# FPGA_power_supply.net
KiCad netlist of a schematic drawn in Altium Designer
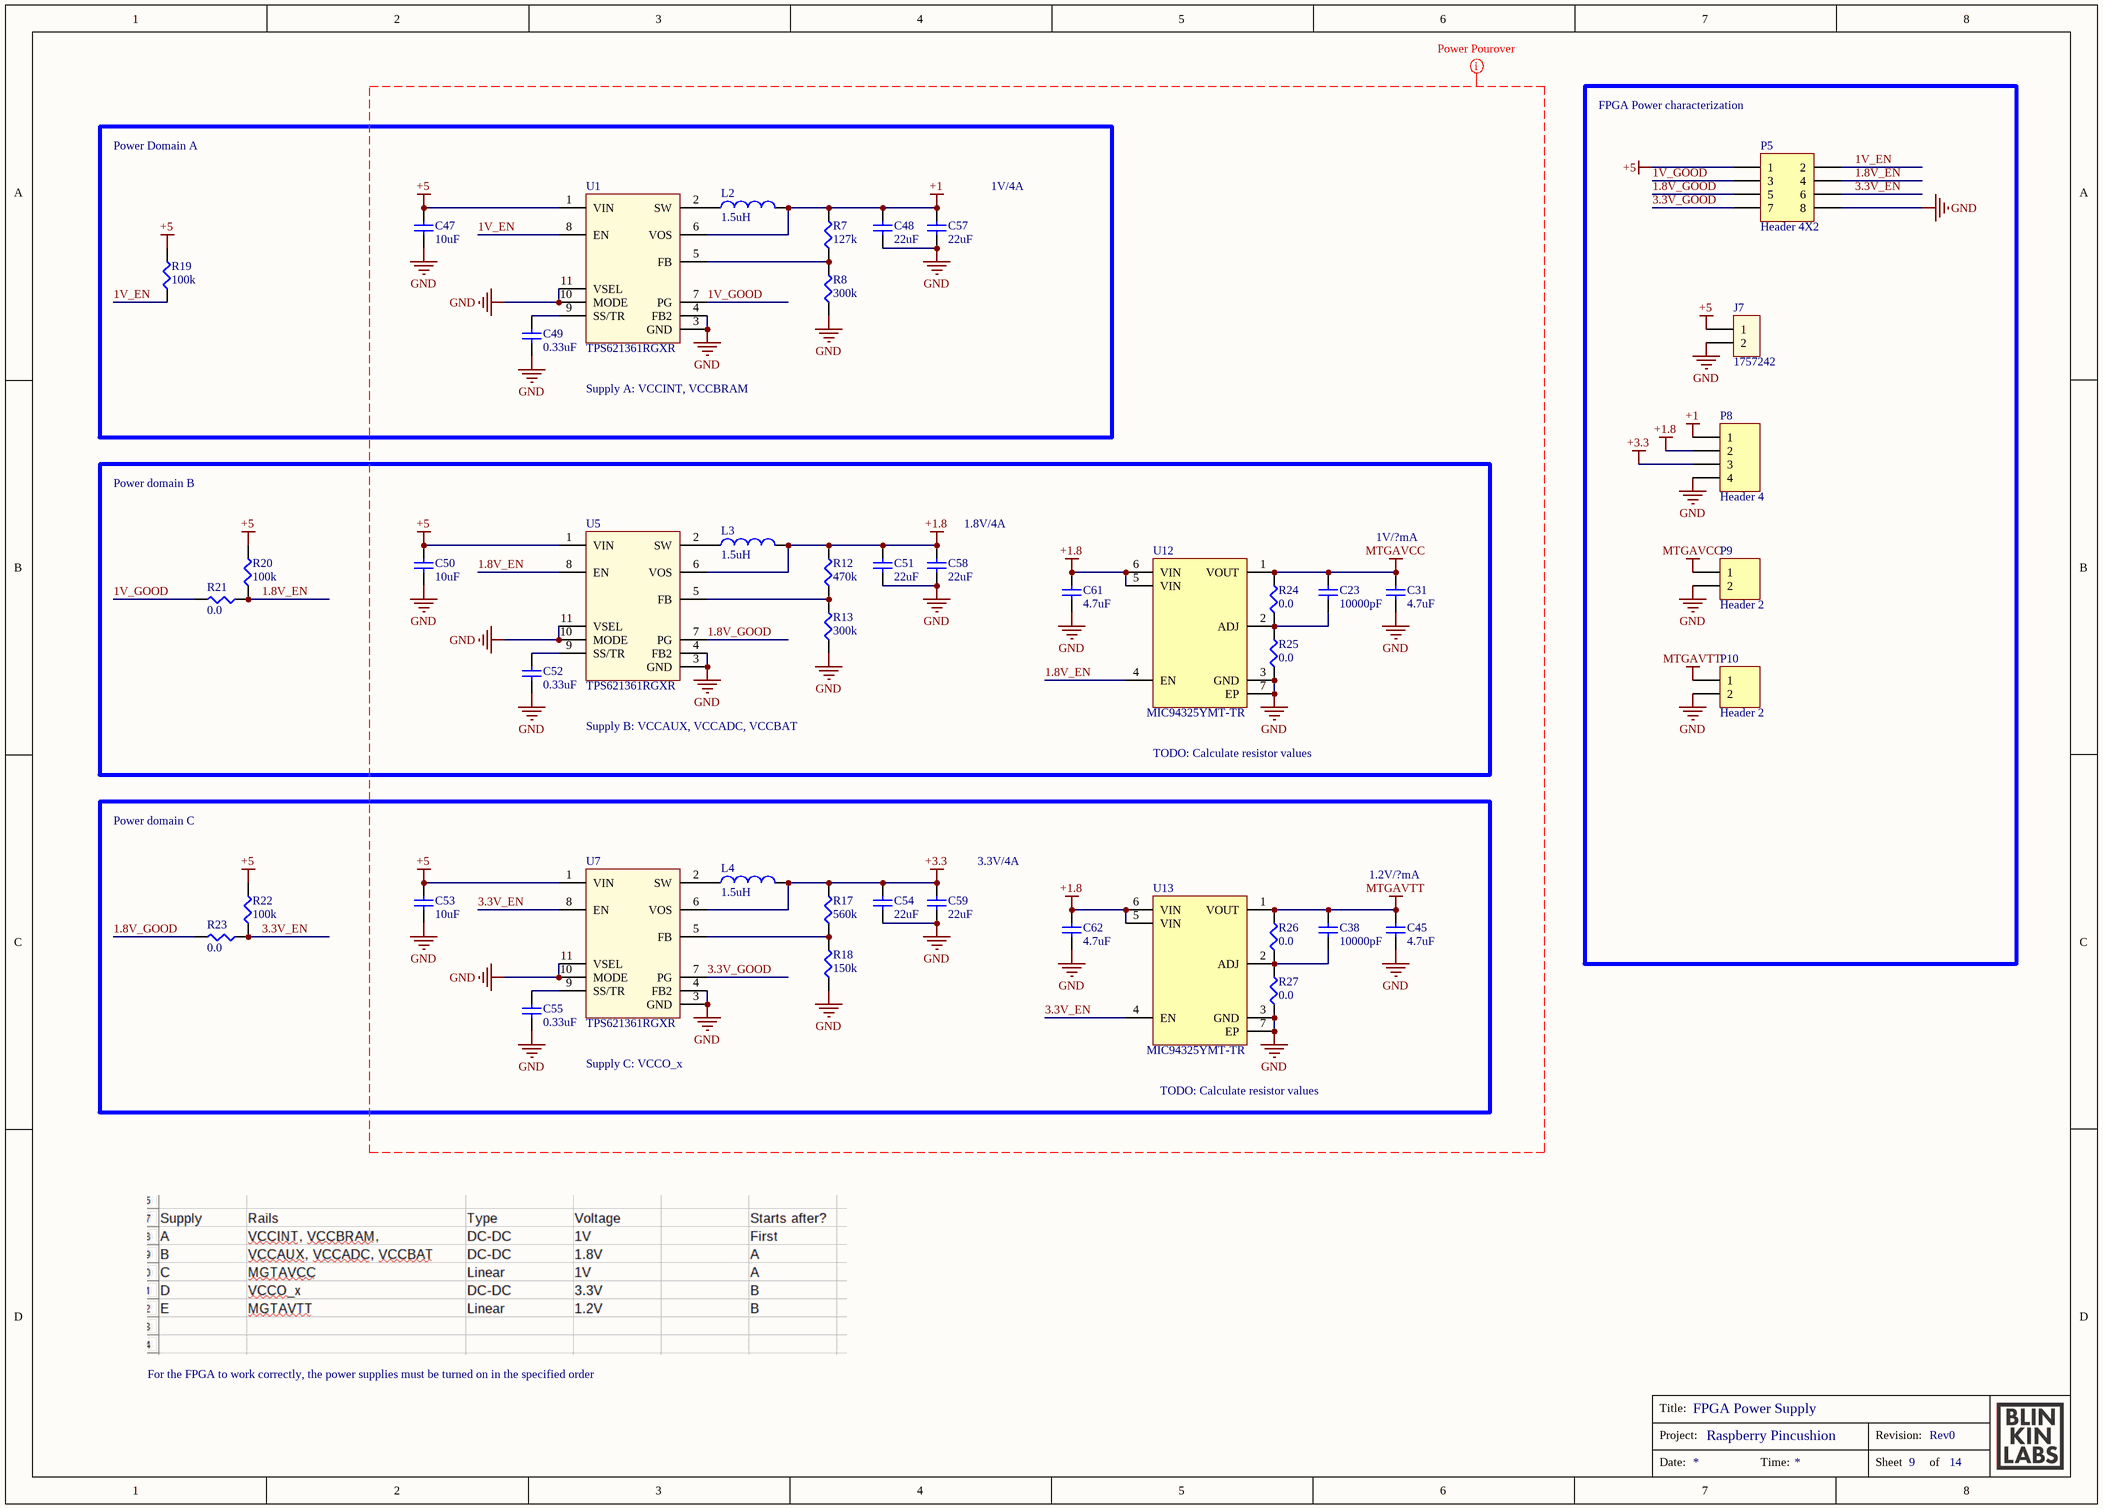
[diagram p0: FPGA power supply.SchDoc]

(export (version "E")
  (design (tool "Eeschema 10.0.6"))
  (components
    (comp (ref "C23")
      (value "10000pF")
      (footprint "CAPC1005X06L")
      (description "CAP CER 10000PF 16V X7R 0402")
      (fields
        (field (name "PARTNUMBER") "GRM155R71C103KA01D")
        (field (name "DIGI-KEY PART NUMBER") "490-1313-1-ND")
      )
      (libsource (lib "cap_murata") (part "CAPACITOR"))
    )
    (comp (ref "C31")
      (value "4.7uF")
      (footprint "CAPC1005X06L")
      (description "CAP CER 4.7UF 4V X5R 0402")
      (fields
        (field (name "PARTNUMBER") "GRM155R60G475ME47D")
        (field (name "DIGI-KEY PART NUMBER") "490-11980-1-ND")
      )
      (libsource (lib "cap_murata") (part "CAPACITOR"))
    )
    (comp (ref "C38")
      (value "10000pF")
      (footprint "CAPC1005X06L")
      (description "CAP CER 10000PF 16V X7R 0402")
      (fields
        (field (name "PARTNUMBER") "GRM155R71C103KA01D")
        (field (name "DIGI-KEY PART NUMBER") "490-1313-1-ND")
      )
      (libsource (lib "cap_murata") (part "CAPACITOR"))
    )
    (comp (ref "C45")
      (value "4.7uF")
      (footprint "CAPC1005X06L")
      (description "CAP CER 4.7UF 4V X5R 0402")
      (fields
        (field (name "PARTNUMBER") "GRM155R60G475ME47D")
        (field (name "DIGI-KEY PART NUMBER") "490-11980-1-ND")
      )
      (libsource (lib "cap_murata") (part "CAPACITOR"))
    )
    (comp (ref "C47")
      (value "10uF")
      (footprint "CAPC2012X10L")
      (description "CAP CER 10UF 10V X7R 0805")
      (fields
        (field (name "PARTNUMBER") "GRM21BR71A106KE51L")
        (field (name "DIGI-KEY PART NUMBER") "490-3905-1-ND")
      )
      (libsource (lib "cap_murata") (part "CAPACITOR"))
    )
    (comp (ref "C48")
      (value "22uF")
      (footprint "CAPC2012X10L")
      (description "CAP CER 22UF 10V X5R 0805")
      (fields
        (field (name "PARTNUMBER") "GRM219R61A226MEA0D")
        (field (name "DIGI-KEY PART NUMBER") "490-9951-1-ND")
      )
      (libsource (lib "cap_murata") (part "CAPACITOR"))
    )
    (comp (ref "C49")
      (value "0.33uF")
      (footprint "CAPC1005X06L")
      (description "CAP CER 0.33UF 6.3V X5R 0402")
      (fields
        (field (name "PARTNUMBER") "GRM155R60J334KE01D")
        (field (name "DIGI-KEY PART NUMBER") "490-3265-1-ND")
      )
      (libsource (lib "cap_murata") (part "CAPACITOR"))
    )
    (comp (ref "C50")
      (value "10uF")
      (footprint "CAPC2012X10L")
      (description "CAP CER 10UF 10V X7R 0805")
      (fields
        (field (name "PARTNUMBER") "GRM21BR71A106KE51L")
        (field (name "DIGI-KEY PART NUMBER") "490-3905-1-ND")
      )
      (libsource (lib "cap_murata") (part "CAPACITOR"))
    )
    (comp (ref "C51")
      (value "22uF")
      (footprint "CAPC2012X10L")
      (description "CAP CER 22UF 10V X5R 0805")
      (fields
        (field (name "PARTNUMBER") "GRM219R61A226MEA0D")
        (field (name "DIGI-KEY PART NUMBER") "490-9951-1-ND")
      )
      (libsource (lib "cap_murata") (part "CAPACITOR"))
    )
    (comp (ref "C52")
      (value "0.33uF")
      (footprint "CAPC1005X06L")
      (description "CAP CER 0.33UF 6.3V X5R 0402")
      (fields
        (field (name "PARTNUMBER") "GRM155R60J334KE01D")
        (field (name "DIGI-KEY PART NUMBER") "490-3265-1-ND")
      )
      (libsource (lib "cap_murata") (part "CAPACITOR"))
    )
    (comp (ref "C53")
      (value "10uF")
      (footprint "CAPC2012X10L")
      (description "CAP CER 10UF 10V X7R 0805")
      (fields
        (field (name "PARTNUMBER") "GRM21BR71A106KE51L")
        (field (name "DIGI-KEY PART NUMBER") "490-3905-1-ND")
      )
      (libsource (lib "cap_murata") (part "CAPACITOR"))
    )
    (comp (ref "C54")
      (value "22uF")
      (footprint "CAPC2012X10L")
      (description "CAP CER 22UF 10V X5R 0805")
      (fields
        (field (name "PARTNUMBER") "GRM219R61A226MEA0D")
        (field (name "DIGI-KEY PART NUMBER") "490-9951-1-ND")
      )
      (libsource (lib "cap_murata") (part "CAPACITOR"))
    )
    (comp (ref "C55")
      (value "0.33uF")
      (footprint "CAPC1005X06L")
      (description "CAP CER 0.33UF 6.3V X5R 0402")
      (fields
        (field (name "PARTNUMBER") "GRM155R60J334KE01D")
        (field (name "DIGI-KEY PART NUMBER") "490-3265-1-ND")
      )
      (libsource (lib "cap_murata") (part "CAPACITOR"))
    )
    (comp (ref "C57")
      (value "22uF")
      (footprint "CAPC2012X10L")
      (description "CAP CER 22UF 10V X5R 0805")
      (fields
        (field (name "PARTNUMBER") "GRM219R61A226MEA0D")
        (field (name "DIGI-KEY PART NUMBER") "490-9951-1-ND")
      )
      (libsource (lib "cap_murata") (part "CAPACITOR"))
    )
    (comp (ref "C58")
      (value "22uF")
      (footprint "CAPC2012X10L")
      (description "CAP CER 22UF 10V X5R 0805")
      (fields
        (field (name "PARTNUMBER") "GRM219R61A226MEA0D")
        (field (name "DIGI-KEY PART NUMBER") "490-9951-1-ND")
      )
      (libsource (lib "cap_murata") (part "CAPACITOR"))
    )
    (comp (ref "C59")
      (value "22uF")
      (footprint "CAPC2012X10L")
      (description "CAP CER 22UF 10V X5R 0805")
      (fields
        (field (name "PARTNUMBER") "GRM219R61A226MEA0D")
        (field (name "DIGI-KEY PART NUMBER") "490-9951-1-ND")
      )
      (libsource (lib "cap_murata") (part "CAPACITOR"))
    )
    (comp (ref "C61")
      (value "4.7uF")
      (footprint "CAPC1005X06L")
      (description "CAP CER 4.7UF 4V X5R 0402")
      (fields
        (field (name "PARTNUMBER") "GRM155R60G475ME47D")
        (field (name "DIGI-KEY PART NUMBER") "490-11980-1-ND")
      )
      (libsource (lib "cap_murata") (part "CAPACITOR"))
    )
    (comp (ref "C62")
      (value "4.7uF")
      (footprint "CAPC1005X06L")
      (description "CAP CER 4.7UF 4V X5R 0402")
      (fields
        (field (name "PARTNUMBER") "GRM155R60G475ME47D")
        (field (name "DIGI-KEY PART NUMBER") "490-11980-1-ND")
      )
      (libsource (lib "cap_murata") (part "CAPACITOR"))
    )
    (comp (ref "J7")
      (value "1757242")
      (footprint "1757242")
      (description "TERM BLOCK HDR 2POS 90DEG 5.08MM")
      (fields (field (name "MANUFACTURER") "Phoenix Contact") (field (name "PARTNUMBER") "1757268"))
      (libsource (lib "Blinkinlabs") (part "1757242"))
    )
    (comp (ref "L2")
      (value "1.5uH")
      (footprint "SWPA4030S")
      (description "1.5uH ±20% 3.34A 26mΩ SMD,4.0x4.0x3.0mm Power Inductors RoHS")
      (fields (field (name "PARTNUMBER") "SWPA4030S1R5NT") (field (name "LCSC PARTNUMBER") "C42100"))
      (libsource (lib "inductor_changjiang") (part "INDUCTOR"))
    )
    (comp (ref "L3")
      (value "1.5uH")
      (footprint "SWPA4030S")
      (description "1.5uH ±20% 3.34A 26mΩ SMD,4.0x4.0x3.0mm Power Inductors RoHS")
      (fields (field (name "PARTNUMBER") "SWPA4030S1R5NT") (field (name "LCSC PARTNUMBER") "C42100"))
      (libsource (lib "inductor_changjiang") (part "INDUCTOR"))
    )
    (comp (ref "L4")
      (value "1.5uH")
      (footprint "SWPA4030S")
      (description "1.5uH ±20% 3.34A 26mΩ SMD,4.0x4.0x3.0mm Power Inductors RoHS")
      (fields (field (name "PARTNUMBER") "SWPA4030S1R5NT") (field (name "LCSC PARTNUMBER") "C42100"))
      (libsource (lib "inductor_changjiang") (part "INDUCTOR"))
    )
    (comp (ref "P5")
      (value "Header 4X2")
      (footprint "HDR2X4")
      (description "Header, 4-Pin, Dual row")
      (fields (field (name "PUBLISHER") "Altium Limited"))
      (libsource (lib "Miscellaneous Connectors") (part "Header 4X2"))
    )
    (comp (ref "P8")
      (value "Header 4")
      (footprint "HDR1X4")
      (description "Header, 4-Pin")
      (fields (field (name "PUBLISHER") "Altium Limited"))
      (libsource (lib "Miscellaneous Connectors") (part "Header 4"))
    )
    (comp (ref "P9")
      (value "Header 2")
      (footprint "HDR1X2")
      (description "Header, 2-Pin")
      (fields (field (name "PUBLISHER") "Altium Limited"))
      (libsource (lib "Miscellaneous Connectors") (part "Header 2"))
    )
    (comp (ref "P10")
      (value "Header 2")
      (footprint "HDR1X2")
      (description "Header, 2-Pin")
      (fields (field (name "PUBLISHER") "Altium Limited"))
      (libsource (lib "Miscellaneous Connectors") (part "Header 2"))
    )
    (comp (ref "R7")
      (value "127k")
      (footprint "ERJ2G(0402)_L")
      (description "RES SMD 127K OHM 1% 1/10W 0402")
      (fields (field (name "PARTNUMBER") "ERJ-2RKF1273X") (field (name "DIGI-KEY PART NUMBER") "P127KLCT-ND"))
      (libsource (lib "res_panasonic_erj_xls") (part "RESISTOR"))
    )
    (comp (ref "R8")
      (value "300k")
      (footprint "ERJ2G(0402)_L")
      (description "RES SMD 300K OHM 1% 1/10W 0402")
      (fields (field (name "PARTNUMBER") "ERJ-2RKF3003X") (field (name "DIGI-KEY PART NUMBER") "P300KLCT-ND"))
      (libsource (lib "res_panasonic_erj_xls") (part "RESISTOR"))
    )
    (comp (ref "R12")
      (value "470k")
      (footprint "ERJ2G(0402)_L")
      (description "RES SMD 470K OHM 1% 1/5W 0402")
      (fields (field (name "PARTNUMBER") "ERJ-PA2F4703X") (field (name "DIGI-KEY PART NUMBER") "P17240CT-ND"))
      (libsource (lib "res_panasonic_erj_xls") (part "RESISTOR"))
    )
    (comp (ref "R13")
      (value "300k")
      (footprint "ERJ2G(0402)_L")
      (description "RES SMD 300K OHM 1% 1/10W 0402")
      (fields (field (name "PARTNUMBER") "ERJ-2RKF3003X") (field (name "DIGI-KEY PART NUMBER") "P300KLCT-ND"))
      (libsource (lib "res_panasonic_erj_xls") (part "RESISTOR"))
    )
    (comp (ref "R17")
      (value "560k")
      (footprint "ERJ2G(0402)_L")
      (description "RES SMD 560K OHM 1% 1/10W 0402")
      (fields (field (name "PARTNUMBER") "ERJ-2RKF5603X") (field (name "DIGI-KEY PART NUMBER") "P560KLCT-ND"))
      (libsource (lib "res_panasonic_erj_xls") (part "RESISTOR"))
    )
    (comp (ref "R18")
      (value "150k")
      (footprint "ERJ2G(0402)_L")
      (description "RES SMD 150K OHM 1% 1/5W 0402")
      (fields (field (name "PARTNUMBER") "ERJ-PA2F1503X") (field (name "DIGI-KEY PART NUMBER") "P17237CT-ND"))
      (libsource (lib "res_panasonic_erj_xls") (part "RESISTOR"))
    )
    (comp (ref "R19")
      (value "100k")
      (footprint "ERJ2G(0402)_L")
      (description "RES SMD 100K OHM 1% 1/5W 0402")
      (fields (field (name "PARTNUMBER") "ERJ-PA2F1003X") (field (name "DIGI-KEY PART NUMBER") "P17236CT-ND"))
      (libsource (lib "res_panasonic_erj_xls") (part "RESISTOR"))
    )
    (comp (ref "R20")
      (value "100k")
      (footprint "ERJ2G(0402)_L")
      (description "RES SMD 100K OHM 1% 1/5W 0402")
      (fields (field (name "PARTNUMBER") "ERJ-PA2F1003X") (field (name "DIGI-KEY PART NUMBER") "P17236CT-ND"))
      (libsource (lib "res_panasonic_erj_xls") (part "RESISTOR"))
    )
    (comp (ref "R21")
      (value "0.0")
      (footprint "ERJ2G(0402)_L")
      (description "RES SMD 0.0OHM JUMPER 1/10W 0402")
      (fields (field (name "PARTNUMBER") "ERJ-2GE0R00X") (field (name "DIGI-KEY PART NUMBER") "P0.0JCT-ND"))
      (libsource (lib "res_panasonic_erj_xls") (part "RESISTOR"))
    )
    (comp (ref "R22")
      (value "100k")
      (footprint "ERJ2G(0402)_L")
      (description "RES SMD 100K OHM 1% 1/5W 0402")
      (fields (field (name "PARTNUMBER") "ERJ-PA2F1003X") (field (name "DIGI-KEY PART NUMBER") "P17236CT-ND"))
      (libsource (lib "res_panasonic_erj_xls") (part "RESISTOR"))
    )
    (comp (ref "R23")
      (value "0.0")
      (footprint "ERJ2G(0402)_L")
      (description "RES SMD 0.0OHM JUMPER 1/10W 0402")
      (fields (field (name "PARTNUMBER") "ERJ-2GE0R00X") (field (name "DIGI-KEY PART NUMBER") "P0.0JCT-ND"))
      (libsource (lib "res_panasonic_erj_xls") (part "RESISTOR"))
    )
    (comp (ref "R24")
      (value "0.0")
      (footprint "ERJ2G(0402)_L")
      (description "RES SMD 0.0OHM JUMPER 1/10W 0402")
      (fields (field (name "PARTNUMBER") "ERJ-2GE0R00X") (field (name "DIGI-KEY PART NUMBER") "P0.0JCT-ND"))
      (libsource (lib "res_panasonic_erj_xls") (part "RESISTOR"))
    )
    (comp (ref "R25")
      (value "0.0")
      (footprint "ERJ2G(0402)_L")
      (description "RES SMD 0.0OHM JUMPER 1/10W 0402")
      (fields (field (name "PARTNUMBER") "ERJ-2GE0R00X") (field (name "DIGI-KEY PART NUMBER") "P0.0JCT-ND"))
      (libsource (lib "res_panasonic_erj_xls") (part "RESISTOR"))
    )
    (comp (ref "R26")
      (value "0.0")
      (footprint "ERJ2G(0402)_L")
      (description "RES SMD 0.0OHM JUMPER 1/10W 0402")
      (fields (field (name "PARTNUMBER") "ERJ-2GE0R00X") (field (name "DIGI-KEY PART NUMBER") "P0.0JCT-ND"))
      (libsource (lib "res_panasonic_erj_xls") (part "RESISTOR"))
    )
    (comp (ref "R27")
      (value "0.0")
      (footprint "ERJ2G(0402)_L")
      (description "RES SMD 0.0OHM JUMPER 1/10W 0402")
      (fields (field (name "PARTNUMBER") "ERJ-2GE0R00X") (field (name "DIGI-KEY PART NUMBER") "P0.0JCT-ND"))
      (libsource (lib "res_panasonic_erj_xls") (part "RESISTOR"))
    )
    (comp (ref "U1")
      (value "TPS621361RGXR")
      (footprint "RGX0011A")
      (description "IC REG BUCK ADJUSTABLE 4A 11VQFN")
      (fields
        (field (name "MANUFACTURER") "Texas Instruments")
        (field (name "DIGIKEY PARTNUMBER") "296-50117-2-ND")
      )
      (libsource (lib "Blinkinlabs") (part "TPS621361RGXR"))
    )
    (comp (ref "U5")
      (value "TPS621361RGXR")
      (footprint "RGX0011A")
      (description "IC REG BUCK ADJUSTABLE 4A 11VQFN")
      (fields
        (field (name "MANUFACTURER") "Texas Instruments")
        (field (name "DIGIKEY PARTNUMBER") "296-50117-2-ND")
      )
      (libsource (lib "Blinkinlabs") (part "TPS621361RGXR"))
    )
    (comp (ref "U7")
      (value "TPS621361RGXR")
      (footprint "RGX0011A")
      (description "IC REG BUCK ADJUSTABLE 4A 11VQFN")
      (fields
        (field (name "MANUFACTURER") "Texas Instruments")
        (field (name "DIGIKEY PARTNUMBER") "296-50117-2-ND")
      )
      (libsource (lib "Blinkinlabs") (part "TPS621361RGXR"))
    )
    (comp (ref "U12")
      (value "MIC94325YMT-TR")
      (footprint "QFN50P160X160X60_HS-7N")
      (description "500mA LDO with  Ripple Blocker Technology")
      (fields
        (field (name "MANUFACTURER") "Microchip Technology")
        (field (name "DIGIKEY PARTNUMBER") "576-4164-2-ND")
      )
      (libsource (lib "Blinkinlabs") (part "MIC94325YMT-TR"))
    )
    (comp (ref "U13")
      (value "MIC94325YMT-TR")
      (footprint "QFN50P160X160X60_HS-7N")
      (description "500mA LDO with  Ripple Blocker Technology")
      (fields
        (field (name "MANUFACTURER") "Microchip Technology")
        (field (name "DIGIKEY PARTNUMBER") "576-4164-2-ND")
      )
      (libsource (lib "Blinkinlabs") (part "MIC94325YMT-TR"))
    )
  )
  (nets
    (net (code "1") (name "+1") (class "Default")
      (node (ref "C48") (pin "1") (pinfunction "1_1") (pintype "passive"))
      (node (ref "C57") (pin "1") (pinfunction "1_1") (pintype "passive"))
      (node (ref "L2") (pin "2") (pinfunction "2_2") (pintype "passive"))
      (node (ref "P8") (pin "1") (pinfunction "1_1") (pintype "passive"))
      (node (ref "R7") (pin "2") (pinfunction "2_2") (pintype "passive"))
      (node (ref "U1") (pin "6") (pinfunction "VOS_6") (pintype "passive"))
    )
    (net (code "2") (name "+1.8") (class "Default")
      (node (ref "C51") (pin "1") (pinfunction "1_1") (pintype "passive"))
      (node (ref "C58") (pin "1") (pinfunction "1_1") (pintype "passive"))
      (node (ref "C61") (pin "2") (pinfunction "2_2") (pintype "passive"))
      (node (ref "C62") (pin "2") (pinfunction "2_2") (pintype "passive"))
      (node (ref "L3") (pin "2") (pinfunction "2_2") (pintype "passive"))
      (node (ref "P8") (pin "2") (pinfunction "2_2") (pintype "passive"))
      (node (ref "R12") (pin "2") (pinfunction "2_2") (pintype "passive"))
      (node (ref "U12") (pin "5") (pinfunction "VIN_5") (pintype "passive"))
      (node (ref "U12") (pin "6") (pinfunction "VIN_6") (pintype "passive"))
      (node (ref "U13") (pin "5") (pinfunction "VIN_5") (pintype "passive"))
      (node (ref "U13") (pin "6") (pinfunction "VIN_6") (pintype "passive"))
      (node (ref "U5") (pin "6") (pinfunction "VOS_6") (pintype "passive"))
    )
    (net (code "3") (name "+3.3") (class "Default")
      (node (ref "C54") (pin "1") (pinfunction "1_1") (pintype "passive"))
      (node (ref "C59") (pin "1") (pinfunction "1_1") (pintype "passive"))
      (node (ref "L4") (pin "2") (pinfunction "2_2") (pintype "passive"))
      (node (ref "P8") (pin "3") (pinfunction "3_3") (pintype "passive"))
      (node (ref "R17") (pin "2") (pinfunction "2_2") (pintype "passive"))
      (node (ref "U7") (pin "6") (pinfunction "VOS_6") (pintype "passive"))
    )
    (net (code "4") (name "+5") (class "Default")
      (node (ref "C47") (pin "1") (pinfunction "1_1") (pintype "passive"))
      (node (ref "C50") (pin "1") (pinfunction "1_1") (pintype "passive"))
      (node (ref "C53") (pin "1") (pinfunction "1_1") (pintype "passive"))
      (node (ref "J7") (pin "1") (pinfunction "1_1") (pintype "passive"))
      (node (ref "P5") (pin "1") (pinfunction "1_1") (pintype "passive"))
      (node (ref "R19") (pin "2") (pinfunction "2_2") (pintype "passive"))
      (node (ref "R20") (pin "2") (pinfunction "2_2") (pintype "passive"))
      (node (ref "R22") (pin "2") (pinfunction "2_2") (pintype "passive"))
      (node (ref "U1") (pin "1") (pinfunction "VIN_1") (pintype "passive"))
      (node (ref "U5") (pin "1") (pinfunction "VIN_1") (pintype "passive"))
      (node (ref "U7") (pin "1") (pinfunction "VIN_1") (pintype "passive"))
    )
    (net (code "5") (name "/1.8V_EN") (class "Default")
      (node (ref "P5") (pin "4") (pinfunction "4_4") (pintype "passive"))
      (node (ref "R20") (pin "1") (pinfunction "1_1") (pintype "passive"))
      (node (ref "R21") (pin "1") (pinfunction "1_1") (pintype "passive"))
      (node (ref "U12") (pin "4") (pinfunction "EN_4") (pintype "passive"))
      (node (ref "U5") (pin "8") (pinfunction "EN_8") (pintype "passive"))
    )
    (net (code "6") (name "/1.8V_GOOD") (class "Default")
      (node (ref "P5") (pin "5") (pinfunction "5_5") (pintype "passive"))
      (node (ref "R23") (pin "2") (pinfunction "2_2") (pintype "passive"))
      (node (ref "U5") (pin "7") (pinfunction "PG_7") (pintype "passive"))
    )
    (net (code "7") (name "/1V_EN") (class "Default")
      (node (ref "P5") (pin "2") (pinfunction "2_2") (pintype "passive"))
      (node (ref "R19") (pin "1") (pinfunction "1_1") (pintype "passive"))
      (node (ref "U1") (pin "8") (pinfunction "EN_8") (pintype "passive"))
    )
    (net (code "8") (name "/1V_GOOD") (class "Default")
      (node (ref "P5") (pin "3") (pinfunction "3_3") (pintype "passive"))
      (node (ref "R21") (pin "2") (pinfunction "2_2") (pintype "passive"))
      (node (ref "U1") (pin "7") (pinfunction "PG_7") (pintype "passive"))
    )
    (net (code "9") (name "/3.3V_EN") (class "Default")
      (node (ref "P5") (pin "6") (pinfunction "6_6") (pintype "passive"))
      (node (ref "R22") (pin "1") (pinfunction "1_1") (pintype "passive"))
      (node (ref "R23") (pin "1") (pinfunction "1_1") (pintype "passive"))
      (node (ref "U13") (pin "4") (pinfunction "EN_4") (pintype "passive"))
      (node (ref "U7") (pin "8") (pinfunction "EN_8") (pintype "passive"))
    )
    (net (code "10") (name "/3.3V_GOOD") (class "Default")
      (node (ref "P5") (pin "7") (pinfunction "7_7") (pintype "passive"))
      (node (ref "U7") (pin "7") (pinfunction "PG_7") (pintype "passive"))
    )
    (net (code "11") (name "GND") (class "Default")
      (node (ref "C31") (pin "1") (pinfunction "1_1") (pintype "passive"))
      (node (ref "C45") (pin "1") (pinfunction "1_1") (pintype "passive"))
      (node (ref "C47") (pin "2") (pinfunction "2_2") (pintype "passive"))
      (node (ref "C48") (pin "2") (pinfunction "2_2") (pintype "passive"))
      (node (ref "C49") (pin "2") (pinfunction "2_2") (pintype "passive"))
      (node (ref "C50") (pin "2") (pinfunction "2_2") (pintype "passive"))
      (node (ref "C51") (pin "2") (pinfunction "2_2") (pintype "passive"))
      (node (ref "C52") (pin "2") (pinfunction "2_2") (pintype "passive"))
      (node (ref "C53") (pin "2") (pinfunction "2_2") (pintype "passive"))
      (node (ref "C54") (pin "2") (pinfunction "2_2") (pintype "passive"))
      (node (ref "C55") (pin "2") (pinfunction "2_2") (pintype "passive"))
      (node (ref "C57") (pin "2") (pinfunction "2_2") (pintype "passive"))
      (node (ref "C58") (pin "2") (pinfunction "2_2") (pintype "passive"))
      (node (ref "C59") (pin "2") (pinfunction "2_2") (pintype "passive"))
      (node (ref "C61") (pin "1") (pinfunction "1_1") (pintype "passive"))
      (node (ref "C62") (pin "1") (pinfunction "1_1") (pintype "passive"))
      (node (ref "J7") (pin "2") (pinfunction "2_2") (pintype "passive"))
      (node (ref "P10") (pin "2") (pinfunction "2_2") (pintype "passive"))
      (node (ref "P5") (pin "8") (pinfunction "8_8") (pintype "passive"))
      (node (ref "P8") (pin "4") (pinfunction "4_4") (pintype "passive"))
      (node (ref "P9") (pin "2") (pinfunction "2_2") (pintype "passive"))
      (node (ref "R13") (pin "1") (pinfunction "1_1") (pintype "passive"))
      (node (ref "R18") (pin "1") (pinfunction "1_1") (pintype "passive"))
      (node (ref "R25") (pin "1") (pinfunction "1_1") (pintype "passive"))
      (node (ref "R27") (pin "1") (pinfunction "1_1") (pintype "passive"))
      (node (ref "R8") (pin "1") (pinfunction "1_1") (pintype "passive"))
      (node (ref "U1") (pin "10") (pinfunction "MODE_10") (pintype "passive"))
      (node (ref "U1") (pin "11") (pinfunction "VSEL_11") (pintype "passive"))
      (node (ref "U1") (pin "3") (pinfunction "GND_3") (pintype "passive"))
      (node (ref "U1") (pin "4") (pinfunction "FB2_4") (pintype "passive"))
      (node (ref "U12") (pin "3") (pinfunction "GND_3") (pintype "passive"))
      (node (ref "U12") (pin "7") (pinfunction "EP_7") (pintype "passive"))
      (node (ref "U13") (pin "3") (pinfunction "GND_3") (pintype "passive"))
      (node (ref "U13") (pin "7") (pinfunction "EP_7") (pintype "passive"))
      (node (ref "U5") (pin "10") (pinfunction "MODE_10") (pintype "passive"))
      (node (ref "U5") (pin "11") (pinfunction "VSEL_11") (pintype "passive"))
      (node (ref "U5") (pin "3") (pinfunction "GND_3") (pintype "passive"))
      (node (ref "U5") (pin "4") (pinfunction "FB2_4") (pintype "passive"))
      (node (ref "U7") (pin "10") (pinfunction "MODE_10") (pintype "passive"))
      (node (ref "U7") (pin "11") (pinfunction "VSEL_11") (pintype "passive"))
      (node (ref "U7") (pin "3") (pinfunction "GND_3") (pintype "passive"))
      (node (ref "U7") (pin "4") (pinfunction "FB2_4") (pintype "passive"))
    )
    (net (code "12") (name "MTGAVCC") (class "Default")
      (node (ref "C23") (pin "1") (pinfunction "1_1") (pintype "passive"))
      (node (ref "C31") (pin "2") (pinfunction "2_2") (pintype "passive"))
      (node (ref "P9") (pin "1") (pinfunction "1_1") (pintype "passive"))
      (node (ref "R24") (pin "2") (pinfunction "2_2") (pintype "passive"))
      (node (ref "U12") (pin "1") (pinfunction "VOUT_1") (pintype "passive"))
    )
    (net (code "13") (name "MTGAVTT") (class "Default")
      (node (ref "C38") (pin "1") (pinfunction "1_1") (pintype "passive"))
      (node (ref "C45") (pin "2") (pinfunction "2_2") (pintype "passive"))
      (node (ref "P10") (pin "1") (pinfunction "1_1") (pintype "passive"))
      (node (ref "R26") (pin "2") (pinfunction "2_2") (pintype "passive"))
      (node (ref "U13") (pin "1") (pinfunction "VOUT_1") (pintype "passive"))
    )
    (net (code "14") (name "Net-(U1-FB)") (class "Default")
      (node (ref "R7") (pin "1") (pinfunction "1_1") (pintype "passive"))
      (node (ref "R8") (pin "2") (pinfunction "2_2") (pintype "passive"))
      (node (ref "U1") (pin "5") (pinfunction "FB_5") (pintype "passive"))
    )
    (net (code "15") (name "Net-(U1-SS{slash}TR)") (class "Default")
      (node (ref "C49") (pin "1") (pinfunction "1_1") (pintype "passive"))
      (node (ref "U1") (pin "9") (pinfunction "SS/TR_9") (pintype "passive"))
    )
    (net (code "16") (name "Net-(U1-SW)") (class "Default")
      (node (ref "L2") (pin "1") (pinfunction "1_1") (pintype "passive"))
      (node (ref "U1") (pin "2") (pinfunction "SW_2") (pintype "passive"))
    )
    (net (code "17") (name "Net-(U5-FB)") (class "Default")
      (node (ref "R12") (pin "1") (pinfunction "1_1") (pintype "passive"))
      (node (ref "R13") (pin "2") (pinfunction "2_2") (pintype "passive"))
      (node (ref "U5") (pin "5") (pinfunction "FB_5") (pintype "passive"))
    )
    (net (code "18") (name "Net-(U5-SS{slash}TR)") (class "Default")
      (node (ref "C52") (pin "1") (pinfunction "1_1") (pintype "passive"))
      (node (ref "U5") (pin "9") (pinfunction "SS/TR_9") (pintype "passive"))
    )
    (net (code "19") (name "Net-(U5-SW)") (class "Default")
      (node (ref "L3") (pin "1") (pinfunction "1_1") (pintype "passive"))
      (node (ref "U5") (pin "2") (pinfunction "SW_2") (pintype "passive"))
    )
    (net (code "20") (name "Net-(U7-FB)") (class "Default")
      (node (ref "R17") (pin "1") (pinfunction "1_1") (pintype "passive"))
      (node (ref "R18") (pin "2") (pinfunction "2_2") (pintype "passive"))
      (node (ref "U7") (pin "5") (pinfunction "FB_5") (pintype "passive"))
    )
    (net (code "21") (name "Net-(U7-SS{slash}TR)") (class "Default")
      (node (ref "C55") (pin "1") (pinfunction "1_1") (pintype "passive"))
      (node (ref "U7") (pin "9") (pinfunction "SS/TR_9") (pintype "passive"))
    )
    (net (code "22") (name "Net-(U7-SW)") (class "Default")
      (node (ref "L4") (pin "1") (pinfunction "1_1") (pintype "passive"))
      (node (ref "U7") (pin "2") (pinfunction "SW_2") (pintype "passive"))
    )
    (net (code "23") (name "Net-(U12-ADJ)") (class "Default")
      (node (ref "C23") (pin "2") (pinfunction "2_2") (pintype "passive"))
      (node (ref "R24") (pin "1") (pinfunction "1_1") (pintype "passive"))
      (node (ref "R25") (pin "2") (pinfunction "2_2") (pintype "passive"))
      (node (ref "U12") (pin "2") (pinfunction "ADJ_2") (pintype "passive"))
    )
    (net (code "24") (name "Net-(U13-ADJ)") (class "Default")
      (node (ref "C38") (pin "2") (pinfunction "2_2") (pintype "passive"))
      (node (ref "R26") (pin "1") (pinfunction "1_1") (pintype "passive"))
      (node (ref "R27") (pin "2") (pinfunction "2_2") (pintype "passive"))
      (node (ref "U13") (pin "2") (pinfunction "ADJ_2") (pintype "passive"))
    )
  )
)
